# PDB.net
KiCad netlist of a schematic drawn in EAGLE
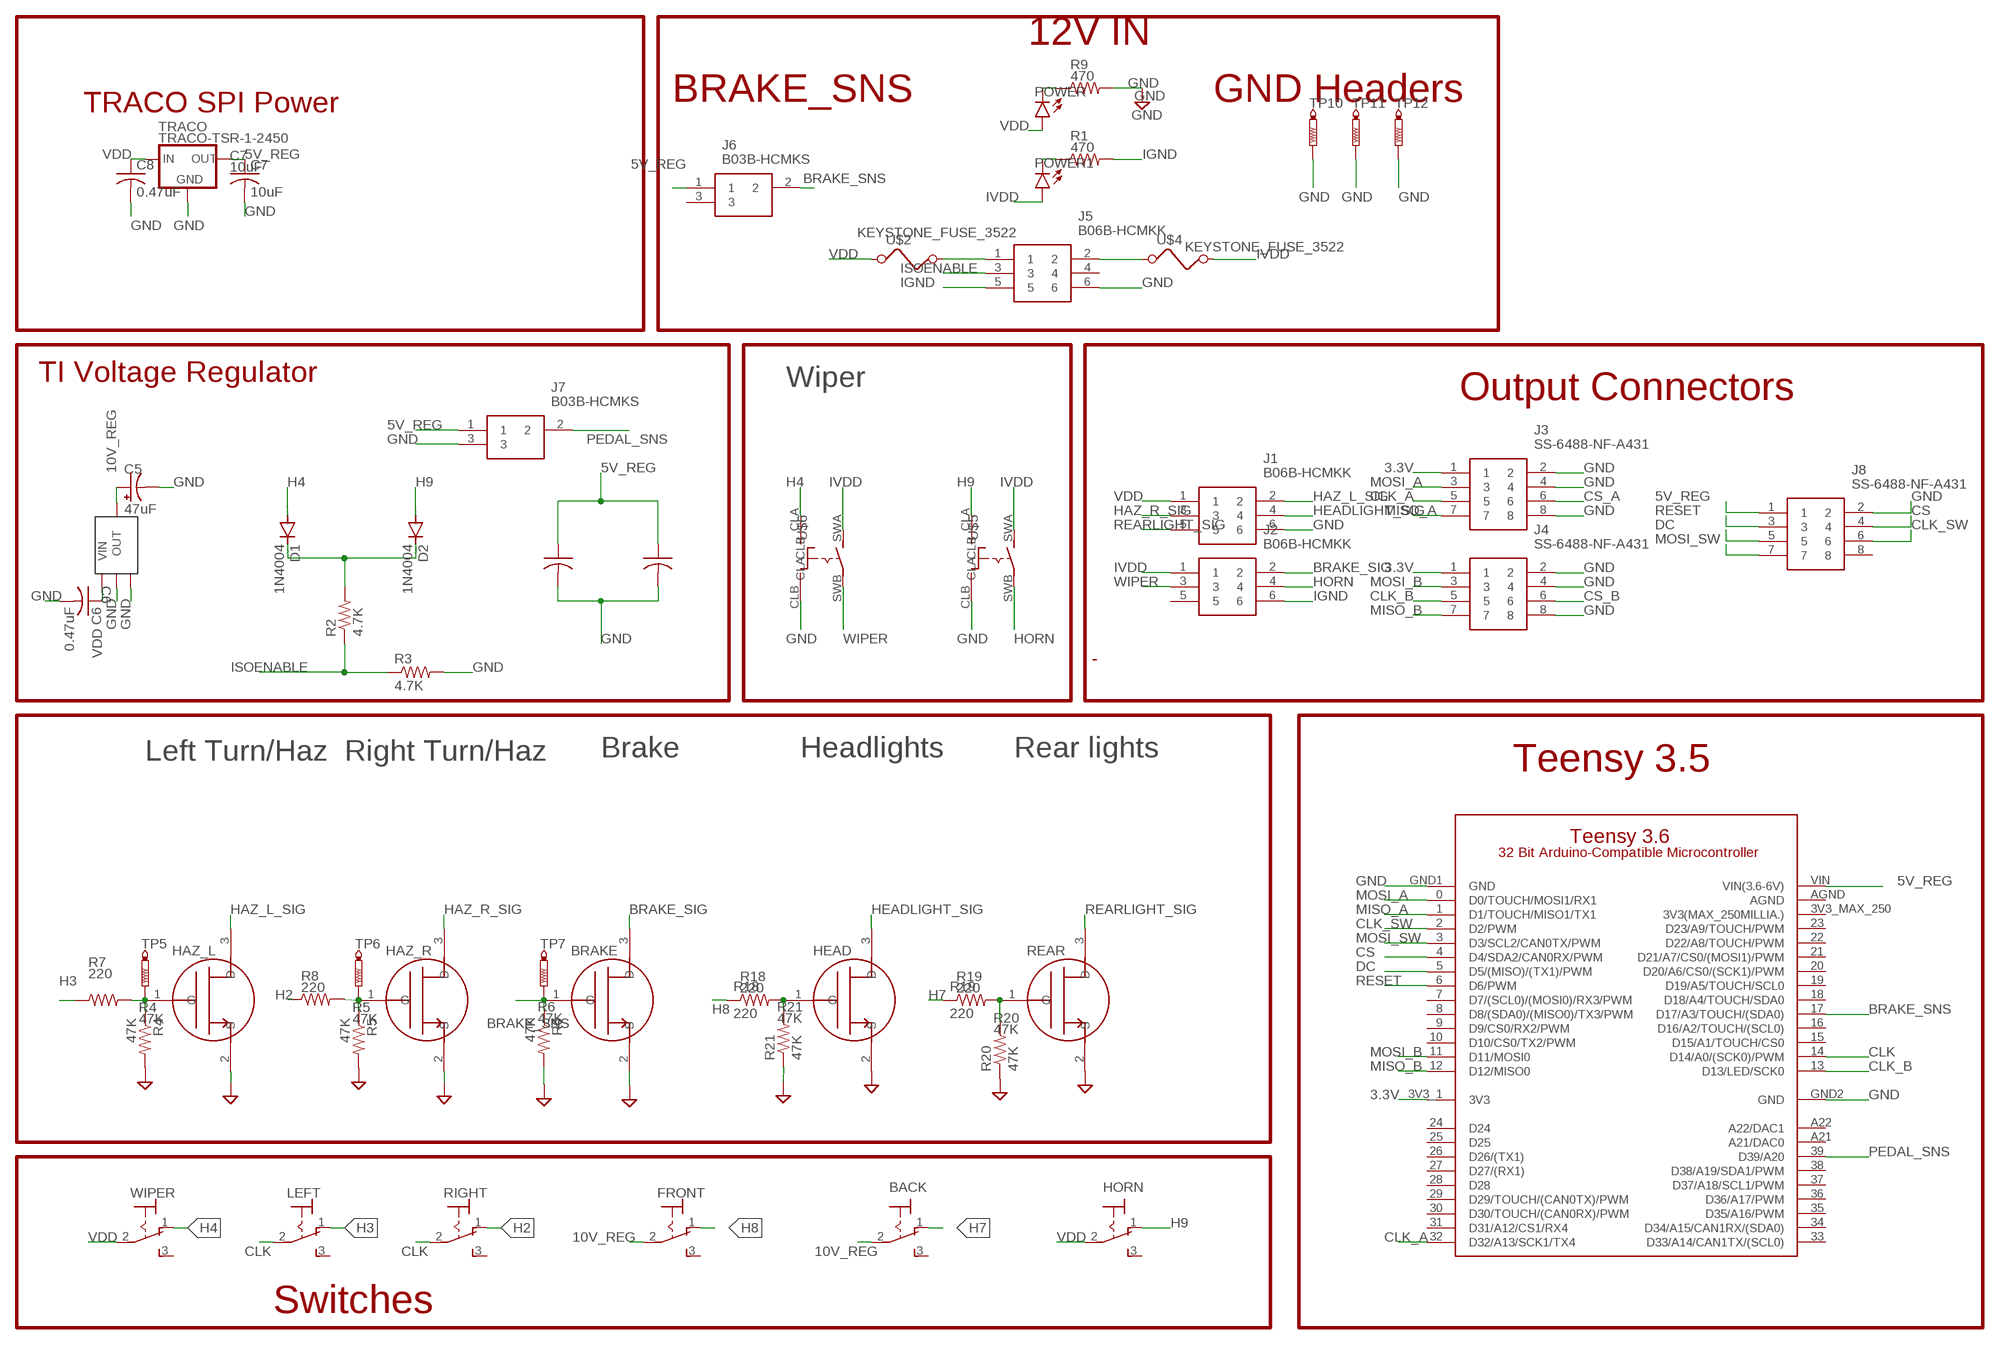
[diagram p0: schematic, sheet 1]

(export (version "E")
  (design (tool "Eeschema 10.0.6"))
  (components
    (comp (ref "BACK")
      (value "M9040P")
      (footprint "eagle-import:M9040P")
      (libsource (lib "eagle-import") (part "M9040P"))
    )
    (comp (ref "BRAKE")
      (value "NCV8405ADPAK-3PIN")
      (footprint "eagle-import:TO254P1054X240-3")
      (libsource (lib "eagle-import") (part "NCV8405ADPAK-3PIN"))
    )
    (comp (ref "C1")
      (value "0.1uF")
      (footprint "eagle-import:C0805")
      (libsource (lib "eagle-import") (part "C-USC0805"))
    )
    (comp (ref "C2")
      (value "10uF")
      (footprint "eagle-import:C0805")
      (libsource (lib "eagle-import") (part "C-USC0805"))
    )
    (comp (ref "C5")
      (value "47uF")
      (footprint "eagle-import:PANASONIC_C")
      (libsource (lib "eagle-import") (part "22UF-POLAR-PANASONIC_C-35V-20%"))
    )
    (comp (ref "C6")
      (value "0.47uF")
      (footprint "eagle-import:C0805")
      (libsource (lib "eagle-import") (part "C-USC0805"))
    )
    (comp (ref "C7")
      (value "10uF")
      (footprint "eagle-import:C0805")
      (libsource (lib "eagle-import") (part "C-USC0805"))
    )
    (comp (ref "C8")
      (value "0.47uF")
      (footprint "eagle-import:C0805")
      (libsource (lib "eagle-import") (part "C-USC0805"))
    )
    (comp (ref "D1")
      (value "1N4004")
      (footprint "eagle-import:DO41-10")
      (libsource (lib "eagle-import") (part "1N4004"))
    )
    (comp (ref "D2")
      (value "1N4004")
      (footprint "eagle-import:DO41-10")
      (libsource (lib "eagle-import") (part "1N4004"))
    )
    (comp (ref "FRONT")
      (value "M9040P")
      (footprint "eagle-import:M9040P")
      (libsource (lib "eagle-import") (part "M9040P"))
    )
    (comp (ref "HAZ_L")
      (value "NCV8405ADPAK-3PIN")
      (footprint "eagle-import:TO254P1054X240-3")
      (libsource (lib "eagle-import") (part "NCV8405ADPAK-3PIN"))
    )
    (comp (ref "HAZ_R")
      (value "NCV8405ADPAK-3PIN")
      (footprint "eagle-import:TO254P1054X240-3")
      (libsource (lib "eagle-import") (part "NCV8405ADPAK-3PIN"))
    )
    (comp (ref "HEAD")
      (value "NCV8405ADPAK-3PIN")
      (footprint "eagle-import:TO254P1054X240-3")
      (libsource (lib "eagle-import") (part "NCV8405ADPAK-3PIN"))
    )
    (comp (ref "HORN")
      (value "M9040P")
      (footprint "eagle-import:M9040P")
      (libsource (lib "eagle-import") (part "M9040P"))
    )
    (comp (ref "J1")
      (value "B06B-HCMKK")
      (footprint "eagle-import:B06BHCMKK")
      (fields (field (name "MOUSER_PART_NUMBER") "306-B06B-HCMKK"))
      (libsource (lib "eagle-import") (part "B06B-HCMKK"))
    )
    (comp (ref "J2")
      (value "B06B-HCMKK")
      (footprint "eagle-import:B06BHCMKK")
      (fields (field (name "MOUSER_PART_NUMBER") "306-B06B-HCMKK"))
      (libsource (lib "eagle-import") (part "B06B-HCMKK"))
    )
    (comp (ref "J3")
      (value "SS-6488-NF-A431")
      (footprint "eagle-import:SS6488NFA431")
      (fields (field (name "MOUSER_PART_NUMBER") "530-SS-6488-NF-A431"))
      (libsource (lib "eagle-import") (part "SS-6488-NF-A431"))
    )
    (comp (ref "J4")
      (value "SS-6488-NF-A431")
      (footprint "eagle-import:SS6488NFA431")
      (fields (field (name "MOUSER_PART_NUMBER") "530-SS-6488-NF-A431"))
      (libsource (lib "eagle-import") (part "SS-6488-NF-A431"))
    )
    (comp (ref "J5")
      (value "B06B-HCMKK")
      (footprint "eagle-import:B06BHCMKK")
      (fields (field (name "MOUSER_PART_NUMBER") "306-B06B-HCMKK"))
      (libsource (lib "eagle-import") (part "B06B-HCMKK"))
    )
    (comp (ref "J6")
      (value "B03B-HCMKS")
      (footprint "eagle-import:B03BHCMKS")
      (fields (field (name "MOUSER_PART_NUMBER") "306-B03B-HCMKS"))
      (libsource (lib "eagle-import") (part "B03B-HCMKS"))
    )
    (comp (ref "J7")
      (value "B03B-HCMKS")
      (footprint "eagle-import:B03BHCMKS")
      (fields (field (name "MOUSER_PART_NUMBER") "306-B03B-HCMKS"))
      (libsource (lib "eagle-import") (part "B03B-HCMKS"))
    )
    (comp (ref "J8")
      (value "SS-6488-NF-A431")
      (footprint "eagle-import:SS6488NFA431")
      (fields (field (name "MOUSER_PART_NUMBER") "530-SS-6488-NF-A431"))
      (libsource (lib "eagle-import") (part "SS-6488-NF-A431"))
    )
    (comp (ref "LEFT")
      (value "M9040P")
      (footprint "eagle-import:M9040P")
      (libsource (lib "eagle-import") (part "M9040P"))
    )
    (comp (ref "LM2940")
      (value "LM2940LM")
      (footprint "eagle-import:SOT230P700X180-4")
      (libsource (lib "eagle-import") (part "LM2940LM"))
    )
    (comp (ref "POWER")
      (value "LEDCHIPLED_0805")
      (footprint "eagle-import:CHIPLED_0805")
      (libsource (lib "eagle-import") (part "LEDCHIPLED_0805"))
    )
    (comp (ref "POWER1")
      (value "LEDCHIPLED_0805")
      (footprint "eagle-import:CHIPLED_0805")
      (libsource (lib "eagle-import") (part "LEDCHIPLED_0805"))
    )
    (comp (ref "R1")
      (value "470")
      (footprint "eagle-import:R3225")
      (libsource (lib "eagle-import") (part "resistor_348_R-US_R3225"))
    )
    (comp (ref "R2")
      (value "4.7K")
      (footprint "eagle-import:R0805")
      (libsource (lib "eagle-import") (part "R-US_R0805"))
    )
    (comp (ref "R3")
      (value "4.7K")
      (footprint "eagle-import:R0805")
      (libsource (lib "eagle-import") (part "R-US_R0805"))
    )
    (comp (ref "R4")
      (value "47K")
      (footprint "eagle-import:R0805")
      (libsource (lib "eagle-import") (part "rcl_334_R-US_R0805"))
    )
    (comp (ref "R5")
      (value "47K")
      (footprint "eagle-import:R0805")
      (libsource (lib "eagle-import") (part "rcl_334_R-US_R0805"))
    )
    (comp (ref "R6")
      (value "47K")
      (footprint "eagle-import:R0805")
      (libsource (lib "eagle-import") (part "rcl_334_R-US_R0805"))
    )
    (comp (ref "R7")
      (value "220")
      (footprint "eagle-import:R0805")
      (libsource (lib "eagle-import") (part "R-US_R0805"))
    )
    (comp (ref "R8")
      (value "220")
      (footprint "eagle-import:R0805")
      (libsource (lib "eagle-import") (part "R-US_R0805"))
    )
    (comp (ref "R9")
      (value "470")
      (footprint "eagle-import:R3225")
      (libsource (lib "eagle-import") (part "resistor_348_R-US_R3225"))
    )
    (comp (ref "R18")
      (value "220")
      (footprint "eagle-import:R0805")
      (libsource (lib "eagle-import") (part "rcl_334_R-US_R0805"))
    )
    (comp (ref "R19")
      (value "220")
      (footprint "eagle-import:R0805")
      (libsource (lib "eagle-import") (part "rcl_334_R-US_R0805"))
    )
    (comp (ref "R20")
      (value "47K")
      (footprint "eagle-import:R0805")
      (libsource (lib "eagle-import") (part "rcl_334_R-US_R0805"))
    )
    (comp (ref "R21")
      (value "47K")
      (footprint "eagle-import:R0805")
      (libsource (lib "eagle-import") (part "rcl_334_R-US_R0805"))
    )
    (comp (ref "REAR")
      (value "NCV8405ADPAK-3PIN")
      (footprint "eagle-import:TO254P1054X240-3")
      (libsource (lib "eagle-import") (part "NCV8405ADPAK-3PIN"))
    )
    (comp (ref "RIGHT")
      (value "M9040P")
      (footprint "eagle-import:M9040P")
      (libsource (lib "eagle-import") (part "M9040P"))
    )
    (comp (ref "TP5")
      (value "PTR1B2,54")
      (footprint "eagle-import:B2,54")
      (libsource (lib "eagle-import") (part "PTR1B2,54"))
    )
    (comp (ref "TP6")
      (value "PTR1B2,54")
      (footprint "eagle-import:B2,54")
      (libsource (lib "eagle-import") (part "PTR1B2,54"))
    )
    (comp (ref "TP7")
      (value "PTR1B2,54")
      (footprint "eagle-import:B2,54")
      (libsource (lib "eagle-import") (part "PTR1B2,54"))
    )
    (comp (ref "TP10")
      (value "PTR1PAD1-13Y")
      (footprint "eagle-import:P1-13Y")
      (libsource (lib "eagle-import") (part "PTR1PAD1-13Y"))
    )
    (comp (ref "TP11")
      (value "PTR1PAD1-13Y")
      (footprint "eagle-import:P1-13Y")
      (libsource (lib "eagle-import") (part "PTR1PAD1-13Y"))
    )
    (comp (ref "TP12")
      (value "PTR1PAD1-13Y")
      (footprint "eagle-import:P1-13Y")
      (libsource (lib "eagle-import") (part "PTR1PAD1-13Y"))
    )
    (comp (ref "TRACO")
      (value "TRACO-TSR-1-2450")
      (footprint "eagle-import:SIP3")
      (libsource (lib "eagle-import") (part "TRACO-TSR-1-2450"))
    )
    (comp (ref "U$2")
      (value "KEYSTONE_FUSE_3522")
      (footprint "eagle-import:KEYSTONE_FUSE_3522")
      (libsource (lib "eagle-import") (part "KEYSTONE_FUSE_3522"))
    )
    (comp (ref "U$3")
      (value "TEENSY-3.6_ONLY_HOLES")
      (footprint "eagle-import:TEENSY-3.6_ONLY_HOLES")
      (libsource (lib "eagle-import") (part "TEENSY-3.6_ONLY_HOLES"))
    )
    (comp (ref "U$4")
      (value "KEYSTONE_FUSE_3522")
      (footprint "eagle-import:KEYSTONE_FUSE_3522")
      (libsource (lib "eagle-import") (part "KEYSTONE_FUSE_3522"))
    )
    (comp (ref "U$5")
      (value "TE_CON_OJE-SH-112DM,095\\")
      (footprint "eagle-import:TE_CON_OJE-SH-112DM,095")
      (libsource (lib "eagle-import") (part "TE_CON_OJE-SH-112DM,095{backslash}"))
    )
    (comp (ref "U$6")
      (value "TE_CON_OJE-SH-112DM,095\\")
      (footprint "eagle-import:TE_CON_OJE-SH-112DM,095")
      (libsource (lib "eagle-import") (part "TE_CON_OJE-SH-112DM,095{backslash}"))
    )
    (comp (ref "WIPER")
      (value "M9040P")
      (footprint "eagle-import:M9040P")
      (libsource (lib "eagle-import") (part "M9040P"))
    )
  )
  (nets
    (net (code "1") (name "3.3V") (class "Default")
      (node (ref "J3") (pin "1") (pinfunction "1_1") (pintype "bidirectional"))
      (node (ref "J4") (pin "1") (pinfunction "1_1") (pintype "bidirectional"))
      (node (ref "U$3") (pin "3V3_1") (pinfunction "3V3_3V3_1") (pintype "power_in"))
    )
    (net (code "2") (name "5V_REG") (class "Default")
      (node (ref "C1") (pin "1") (pinfunction "1_1") (pintype "passive"))
      (node (ref "C2") (pin "1") (pinfunction "1_1") (pintype "passive"))
      (node (ref "C7") (pin "1") (pinfunction "1_1") (pintype "passive"))
      (node (ref "J6") (pin "1") (pinfunction "1_1") (pintype "bidirectional"))
      (node (ref "J7") (pin "1") (pinfunction "1_1") (pintype "bidirectional"))
      (node (ref "J8") (pin "1") (pinfunction "1_1") (pintype "bidirectional"))
      (node (ref "TRACO") (pin "3") (pinfunction "OUT_3") (pintype "passive"))
      (node (ref "U$3") (pin "VIN") (pinfunction "VIN(3.6-6V)_VIN") (pintype "power_in"))
    )
    (net (code "3") (name "10V_REG") (class "Default")
      (node (ref "BACK") (pin "2") (pinfunction "P_2") (pintype "passive"))
      (node (ref "C5") (pin "+") (pinfunction "+_+") (pintype "passive"))
      (node (ref "FRONT") (pin "2") (pinfunction "P_2") (pintype "passive"))
      (node (ref "LM2940") (pin "3") (pinfunction "OUT_3") (pintype "output"))
    )
    (net (code "4") (name "AGND") (class "Default")
      (node (ref "U$3") (pin "AGND") (pinfunction "AGND_AGND") (pintype "power_in"))
    )
    (net (code "5") (name "BRAKE_SIG") (class "Default")
      (node (ref "BRAKE") (pin "3") (pinfunction "D_3") (pintype "bidirectional"))
      (node (ref "J2") (pin "2") (pinfunction "2_2") (pintype "bidirectional"))
    )
    (net (code "6") (name "BRAKE_SNS") (class "Default")
      (node (ref "BRAKE") (pin "1") (pinfunction "G_1") (pintype "bidirectional"))
      (node (ref "J6") (pin "2") (pinfunction "2_2") (pintype "bidirectional"))
      (node (ref "R6") (pin "1") (pinfunction "1_1") (pintype "passive"))
      (node (ref "TP7") (pin "TP") (pinfunction "TP_TP") (pintype "input"))
      (node (ref "U$3") (pin "17") (pinfunction "D17/A3/TOUCH/(SDA0)_17") (pintype "bidirectional"))
    )
    (net (code "7") (name "CLK") (class "Default")
      (node (ref "LEFT") (pin "2") (pinfunction "P_2") (pintype "passive"))
      (node (ref "RIGHT") (pin "2") (pinfunction "P_2") (pintype "passive"))
      (node (ref "U$3") (pin "14") (pinfunction "D14/A0/(SCK0)/PWM_14") (pintype "bidirectional"))
    )
    (net (code "8") (name "CLK_A") (class "Default")
      (node (ref "J3") (pin "5") (pinfunction "5_5") (pintype "bidirectional"))
      (node (ref "U$3") (pin "32") (pinfunction "D32/A13/SCK1/TX4_32") (pintype "bidirectional"))
    )
    (net (code "9") (name "CLK_B") (class "Default")
      (node (ref "J4") (pin "5") (pinfunction "5_5") (pintype "bidirectional"))
      (node (ref "U$3") (pin "13") (pinfunction "D13/LED/SCK0_13") (pintype "bidirectional"))
    )
    (net (code "10") (name "CLK_SW") (class "Default")
      (node (ref "J8") (pin "6") (pinfunction "6_6") (pintype "bidirectional"))
      (node (ref "U$3") (pin "2") (pinfunction "D2/PWM_2") (pintype "bidirectional"))
    )
    (net (code "11") (name "CS") (class "Default")
      (node (ref "J8") (pin "4") (pinfunction "4_4") (pintype "bidirectional"))
      (node (ref "U$3") (pin "4") (pinfunction "D4/SDA2/CAN0RX/PWM_4") (pintype "bidirectional"))
    )
    (net (code "12") (name "CS_A") (class "Default")
      (node (ref "J3") (pin "6") (pinfunction "6_6") (pintype "bidirectional"))
    )
    (net (code "13") (name "CS_B") (class "Default")
      (node (ref "J4") (pin "6") (pinfunction "6_6") (pintype "bidirectional"))
    )
    (net (code "14") (name "DC") (class "Default")
      (node (ref "J8") (pin "5") (pinfunction "5_5") (pintype "bidirectional"))
      (node (ref "U$3") (pin "5") (pinfunction "D5/(MISO)/(TX1)/PWM_5") (pintype "bidirectional"))
    )
    (net (code "15") (name "GND") (class "Default")
      (node (ref "BRAKE") (pin "2") (pinfunction "S_2") (pintype "bidirectional"))
      (node (ref "C1") (pin "2") (pinfunction "2_2") (pintype "passive"))
      (node (ref "C2") (pin "2") (pinfunction "2_2") (pintype "passive"))
      (node (ref "C5") (pin "-") (pinfunction "-_-") (pintype "passive"))
      (node (ref "C6") (pin "2") (pinfunction "2_2") (pintype "passive"))
      (node (ref "C7") (pin "2") (pinfunction "2_2") (pintype "passive"))
      (node (ref "C8") (pin "2") (pinfunction "2_2") (pintype "passive"))
      (node (ref "HAZ_L") (pin "2") (pinfunction "S_2") (pintype "bidirectional"))
      (node (ref "HAZ_R") (pin "2") (pinfunction "S_2") (pintype "bidirectional"))
      (node (ref "HEAD") (pin "2") (pinfunction "S_2") (pintype "bidirectional"))
      (node (ref "J1") (pin "6") (pinfunction "6_6") (pintype "bidirectional"))
      (node (ref "J3") (pin "2") (pinfunction "2_2") (pintype "bidirectional"))
      (node (ref "J3") (pin "4") (pinfunction "4_4") (pintype "bidirectional"))
      (node (ref "J3") (pin "8") (pinfunction "8_8") (pintype "bidirectional"))
      (node (ref "J4") (pin "2") (pinfunction "2_2") (pintype "bidirectional"))
      (node (ref "J4") (pin "4") (pinfunction "4_4") (pintype "bidirectional"))
      (node (ref "J4") (pin "8") (pinfunction "8_8") (pintype "bidirectional"))
      (node (ref "J5") (pin "6") (pinfunction "6_6") (pintype "bidirectional"))
      (node (ref "J7") (pin "3") (pinfunction "3_3") (pintype "bidirectional"))
      (node (ref "J8") (pin "2") (pinfunction "2_2") (pintype "bidirectional"))
      (node (ref "LM2940") (pin "2") (pinfunction "GND2_2") (pintype "power_in"))
      (node (ref "LM2940") (pin "4") (pinfunction "GND_4") (pintype "power_in"))
      (node (ref "R20") (pin "1") (pinfunction "1_1") (pintype "passive"))
      (node (ref "R21") (pin "1") (pinfunction "1_1") (pintype "passive"))
      (node (ref "R3") (pin "2") (pinfunction "2_2") (pintype "passive"))
      (node (ref "R4") (pin "2") (pinfunction "2_2") (pintype "passive"))
      (node (ref "R5") (pin "2") (pinfunction "2_2") (pintype "passive"))
      (node (ref "R6") (pin "2") (pinfunction "2_2") (pintype "passive"))
      (node (ref "R9") (pin "2") (pinfunction "2_2") (pintype "passive"))
      (node (ref "REAR") (pin "2") (pinfunction "S_2") (pintype "bidirectional"))
      (node (ref "TP10") (pin "TP") (pinfunction "TP_TP") (pintype "input"))
      (node (ref "TP11") (pin "TP") (pinfunction "TP_TP") (pintype "input"))
      (node (ref "TP12") (pin "TP") (pinfunction "TP_TP") (pintype "input"))
      (node (ref "TRACO") (pin "2") (pinfunction "GND_2") (pintype "input"))
      (node (ref "U$3") (pin "GND1") (pinfunction "GND_GND1") (pintype "power_in"))
      (node (ref "U$3") (pin "GND2") (pinfunction "GND_GND2") (pintype "power_in"))
      (node (ref "U$5") (pin "CLB") (pinfunction "CLB_CLB") (pintype "bidirectional"))
      (node (ref "U$6") (pin "CLB") (pinfunction "CLB_CLB") (pintype "bidirectional"))
    )
    (net (code "16") (name "H2") (class "Default")
      (node (ref "R8") (pin "1") (pinfunction "1_1") (pintype "passive"))
      (node (ref "RIGHT") (pin "1") (pinfunction "O_1") (pintype "passive"))
    )
    (net (code "17") (name "H3") (class "Default")
      (node (ref "LEFT") (pin "1") (pinfunction "O_1") (pintype "passive"))
      (node (ref "R7") (pin "1") (pinfunction "1_1") (pintype "passive"))
    )
    (net (code "18") (name "H4") (class "Default")
      (node (ref "D1") (pin "A") (pinfunction "A_A") (pintype "passive"))
      (node (ref "U$6") (pin "CLA") (pinfunction "CLA_CLA") (pintype "bidirectional"))
      (node (ref "WIPER") (pin "1") (pinfunction "O_1") (pintype "passive"))
    )
    (net (code "19") (name "H7") (class "Default")
      (node (ref "BACK") (pin "1") (pinfunction "O_1") (pintype "passive"))
      (node (ref "R19") (pin "1") (pinfunction "1_1") (pintype "passive"))
    )
    (net (code "20") (name "H8") (class "Default")
      (node (ref "FRONT") (pin "1") (pinfunction "O_1") (pintype "passive"))
      (node (ref "R18") (pin "1") (pinfunction "1_1") (pintype "passive"))
    )
    (net (code "21") (name "H9") (class "Default")
      (node (ref "D2") (pin "A") (pinfunction "A_A") (pintype "passive"))
      (node (ref "HORN") (pin "1") (pinfunction "O_1") (pintype "passive"))
      (node (ref "U$5") (pin "CLA") (pinfunction "CLA_CLA") (pintype "bidirectional"))
    )
    (net (code "22") (name "HAZ_L_SIG") (class "Default")
      (node (ref "HAZ_L") (pin "3") (pinfunction "D_3") (pintype "bidirectional"))
      (node (ref "J1") (pin "2") (pinfunction "2_2") (pintype "bidirectional"))
    )
    (net (code "23") (name "HAZ_R_SIG") (class "Default")
      (node (ref "HAZ_R") (pin "3") (pinfunction "D_3") (pintype "bidirectional"))
      (node (ref "J1") (pin "3") (pinfunction "3_3") (pintype "bidirectional"))
    )
    (net (code "24") (name "HEADLIGHT_SIG") (class "Default")
      (node (ref "HEAD") (pin "3") (pinfunction "D_3") (pintype "bidirectional"))
      (node (ref "J1") (pin "4") (pinfunction "4_4") (pintype "bidirectional"))
    )
    (net (code "25") (name "HORN") (class "Default")
      (node (ref "J2") (pin "4") (pinfunction "4_4") (pintype "bidirectional"))
      (node (ref "U$5") (pin "SWB") (pinfunction "SWB_SWB") (pintype "passive"))
    )
    (net (code "26") (name "IGND") (class "Default")
      (node (ref "J2") (pin "6") (pinfunction "6_6") (pintype "bidirectional"))
      (node (ref "J5") (pin "5") (pinfunction "5_5") (pintype "bidirectional"))
      (node (ref "R1") (pin "2") (pinfunction "2_2") (pintype "passive"))
    )
    (net (code "27") (name "ISOENABLE") (class "Default")
      (node (ref "J5") (pin "3") (pinfunction "3_3") (pintype "bidirectional"))
      (node (ref "R2") (pin "1") (pinfunction "1_1") (pintype "passive"))
      (node (ref "R3") (pin "1") (pinfunction "1_1") (pintype "passive"))
    )
    (net (code "28") (name "IVDD") (class "Default")
      (node (ref "J2") (pin "1") (pinfunction "1_1") (pintype "bidirectional"))
      (node (ref "POWER1") (pin "A") (pinfunction "A_A") (pintype "passive"))
      (node (ref "U$4") (pin "B1") (pinfunction "2_B1") (pintype "passive"))
      (node (ref "U$4") (pin "B2") (pinfunction "2_B2") (pintype "passive"))
      (node (ref "U$5") (pin "SWA") (pinfunction "SWA_SWA") (pintype "passive"))
      (node (ref "U$6") (pin "SWA") (pinfunction "SWA_SWA") (pintype "passive"))
    )
    (net (code "29") (name "MISO_A") (class "Default")
      (node (ref "J3") (pin "7") (pinfunction "7_7") (pintype "bidirectional"))
      (node (ref "U$3") (pin "1") (pinfunction "D1/TOUCH/MISO1/TX1_1") (pintype "bidirectional"))
    )
    (net (code "30") (name "MISO_B") (class "Default")
      (node (ref "J4") (pin "7") (pinfunction "7_7") (pintype "bidirectional"))
      (node (ref "U$3") (pin "12") (pinfunction "D12/MISO0_12") (pintype "bidirectional"))
    )
    (net (code "31") (name "MOSI_A") (class "Default")
      (node (ref "J3") (pin "3") (pinfunction "3_3") (pintype "bidirectional"))
      (node (ref "U$3") (pin "0") (pinfunction "D0/TOUCH/MOSI1/RX1_0") (pintype "bidirectional"))
    )
    (net (code "32") (name "MOSI_B") (class "Default")
      (node (ref "J4") (pin "3") (pinfunction "3_3") (pintype "bidirectional"))
      (node (ref "U$3") (pin "11") (pinfunction "D11/MOSI0_11") (pintype "bidirectional"))
    )
    (net (code "33") (name "MOSI_SW") (class "Default")
      (node (ref "J8") (pin "7") (pinfunction "7_7") (pintype "bidirectional"))
      (node (ref "U$3") (pin "3") (pinfunction "D3/SCL2/CAN0TX/PWM_3") (pintype "bidirectional"))
    )
    (net (code "34") (name "Net-(D1-PadC)") (class "Default")
      (node (ref "D1") (pin "C") (pinfunction "C_C") (pintype "passive"))
      (node (ref "D2") (pin "C") (pinfunction "C_C") (pintype "passive"))
      (node (ref "R2") (pin "2") (pinfunction "2_2") (pintype "passive"))
    )
    (net (code "35") (name "Net-(HAZ_L-G)") (class "Default")
      (node (ref "HAZ_L") (pin "1") (pinfunction "G_1") (pintype "bidirectional"))
      (node (ref "R4") (pin "1") (pinfunction "1_1") (pintype "passive"))
      (node (ref "R7") (pin "2") (pinfunction "2_2") (pintype "passive"))
      (node (ref "TP5") (pin "TP") (pinfunction "TP_TP") (pintype "input"))
    )
    (net (code "36") (name "Net-(HAZ_R-G)") (class "Default")
      (node (ref "HAZ_R") (pin "1") (pinfunction "G_1") (pintype "bidirectional"))
      (node (ref "R5") (pin "1") (pinfunction "1_1") (pintype "passive"))
      (node (ref "R8") (pin "2") (pinfunction "2_2") (pintype "passive"))
      (node (ref "TP6") (pin "TP") (pinfunction "TP_TP") (pintype "input"))
    )
    (net (code "37") (name "Net-(HEAD-G)") (class "Default")
      (node (ref "HEAD") (pin "1") (pinfunction "G_1") (pintype "bidirectional"))
      (node (ref "R18") (pin "2") (pinfunction "2_2") (pintype "passive"))
      (node (ref "R21") (pin "2") (pinfunction "2_2") (pintype "passive"))
    )
    (net (code "38") (name "Net-(J5-Pad1)") (class "Default")
      (node (ref "J5") (pin "1") (pinfunction "1_1") (pintype "bidirectional"))
      (node (ref "U$2") (pin "B1") (pinfunction "2_B1") (pintype "passive"))
      (node (ref "U$2") (pin "B2") (pinfunction "2_B2") (pintype "passive"))
    )
    (net (code "39") (name "Net-(J5-Pad2)") (class "Default")
      (node (ref "J5") (pin "2") (pinfunction "2_2") (pintype "bidirectional"))
      (node (ref "U$4") (pin "A1") (pinfunction "1_A1") (pintype "passive"))
      (node (ref "U$4") (pin "A2") (pinfunction "1_A2") (pintype "passive"))
    )
    (net (code "40") (name "Net-(POWER-PadC)") (class "Default")
      (node (ref "POWER") (pin "C") (pinfunction "C_C") (pintype "passive"))
      (node (ref "R9") (pin "1") (pinfunction "1_1") (pintype "passive"))
    )
    (net (code "41") (name "Net-(POWER1-PadC)") (class "Default")
      (node (ref "POWER1") (pin "C") (pinfunction "C_C") (pintype "passive"))
      (node (ref "R1") (pin "1") (pinfunction "1_1") (pintype "passive"))
    )
    (net (code "42") (name "Net-(REAR-G)") (class "Default")
      (node (ref "R19") (pin "2") (pinfunction "2_2") (pintype "passive"))
      (node (ref "R20") (pin "2") (pinfunction "2_2") (pintype "passive"))
      (node (ref "REAR") (pin "1") (pinfunction "G_1") (pintype "bidirectional"))
    )
    (net (code "43") (name "PEDAL_SNS") (class "Default")
      (node (ref "J7") (pin "2") (pinfunction "2_2") (pintype "bidirectional"))
      (node (ref "U$3") (pin "39") (pinfunction "D39/A20_39") (pintype "bidirectional"))
    )
    (net (code "44") (name "REARLIGHT_SIG") (class "Default")
      (node (ref "J1") (pin "5") (pinfunction "5_5") (pintype "bidirectional"))
      (node (ref "REAR") (pin "3") (pinfunction "D_3") (pintype "bidirectional"))
    )
    (net (code "45") (name "RESET") (class "Default")
      (node (ref "J8") (pin "3") (pinfunction "3_3") (pintype "bidirectional"))
      (node (ref "U$3") (pin "6") (pinfunction "D6/PWM_6") (pintype "bidirectional"))
    )
    (net (code "46") (name "VDD") (class "Default")
      (node (ref "C6") (pin "1") (pinfunction "1_1") (pintype "passive"))
      (node (ref "C8") (pin "1") (pinfunction "1_1") (pintype "passive"))
      (node (ref "HORN") (pin "2") (pinfunction "P_2") (pintype "passive"))
      (node (ref "J1") (pin "1") (pinfunction "1_1") (pintype "bidirectional"))
      (node (ref "LM2940") (pin "1") (pinfunction "VIN_1") (pintype "input"))
      (node (ref "POWER") (pin "A") (pinfunction "A_A") (pintype "passive"))
      (node (ref "TRACO") (pin "1") (pinfunction "IN_1") (pintype "input"))
      (node (ref "U$2") (pin "A1") (pinfunction "1_A1") (pintype "passive"))
      (node (ref "U$2") (pin "A2") (pinfunction "1_A2") (pintype "passive"))
      (node (ref "WIPER") (pin "2") (pinfunction "P_2") (pintype "passive"))
    )
    (net (code "47") (name "WIPER") (class "Default")
      (node (ref "J2") (pin "3") (pinfunction "3_3") (pintype "bidirectional"))
      (node (ref "U$6") (pin "SWB") (pinfunction "SWB_SWB") (pintype "passive"))
    )
    (net (code "48") (name "unconnected-(BACK-S-Pad3)") (class "Default")
      (node (ref "BACK") (pin "3") (pinfunction "S_3") (pintype "passive"))
    )
    (net (code "49") (name "unconnected-(FRONT-S-Pad3)") (class "Default")
      (node (ref "FRONT") (pin "3") (pinfunction "S_3") (pintype "passive"))
    )
    (net (code "50") (name "unconnected-(HORN-S-Pad3)") (class "Default")
      (node (ref "HORN") (pin "3") (pinfunction "S_3") (pintype "passive"))
    )
    (net (code "51") (name "unconnected-(J2-Pad5)") (class "Default")
      (node (ref "J2") (pin "5") (pinfunction "5_5") (pintype "bidirectional"))
    )
    (net (code "52") (name "unconnected-(J5-Pad4)") (class "Default")
      (node (ref "J5") (pin "4") (pinfunction "4_4") (pintype "bidirectional"))
    )
    (net (code "53") (name "unconnected-(J6-Pad3)") (class "Default")
      (node (ref "J6") (pin "3") (pinfunction "3_3") (pintype "bidirectional"))
    )
    (net (code "54") (name "unconnected-(J8-Pad8)") (class "Default")
      (node (ref "J8") (pin "8") (pinfunction "8_8") (pintype "bidirectional"))
    )
    (net (code "55") (name "unconnected-(LEFT-S-Pad3)") (class "Default")
      (node (ref "LEFT") (pin "3") (pinfunction "S_3") (pintype "passive"))
    )
    (net (code "56") (name "unconnected-(RIGHT-S-Pad3)") (class "Default")
      (node (ref "RIGHT") (pin "3") (pinfunction "S_3") (pintype "passive"))
    )
    (net (code "57") (name "unconnected-(U$3-3V3(MAX_250MILLIA.)-Pad3V3_MAX_250)") (class "Default")
      (node (ref "U$3") (pin "3V3_MAX_250") (pinfunction "3V3(MAX_250MILLIA.)_3V3_MAX_250") (pintype "bidirectional"))
    )
    (net (code "58") (name "unconnected-(U$3-A21{slash}DAC0-PadA21)") (class "Default")
      (node (ref "U$3") (pin "A21") (pinfunction "A21/DAC0_A21") (pintype "bidirectional"))
    )
    (net (code "59") (name "unconnected-(U$3-A22{slash}DAC1-PadA22)") (class "Default")
      (node (ref "U$3") (pin "A22") (pinfunction "A22/DAC1_A22") (pintype "bidirectional"))
    )
    (net (code "60") (name "unconnected-(U$3-D7{slash}(SCL0){slash}(MOSI0){slash}RX3{slash}PWM-Pad7)") (class "Default")
      (node (ref "U$3") (pin "7") (pinfunction "D7/(SCL0)/(MOSI0)/RX3/PWM_7") (pintype "bidirectional"))
    )
    (net (code "61") (name "unconnected-(U$3-D8{slash}(SDA0){slash}(MISO0){slash}TX3{slash}PWM-Pad8)") (class "Default")
      (node (ref "U$3") (pin "8") (pinfunction "D8/(SDA0)/(MISO0)/TX3/PWM_8") (pintype "bidirectional"))
    )
    (net (code "62") (name "unconnected-(U$3-D9{slash}CS0{slash}RX2{slash}PWM-Pad9)") (class "Default")
      (node (ref "U$3") (pin "9") (pinfunction "D9/CS0/RX2/PWM_9") (pintype "bidirectional"))
    )
    (net (code "63") (name "unconnected-(U$3-D10{slash}CS0{slash}TX2{slash}PWM-Pad10)") (class "Default")
      (node (ref "U$3") (pin "10") (pinfunction "D10/CS0/TX2/PWM_10") (pintype "bidirectional"))
    )
    (net (code "64") (name "unconnected-(U$3-D15{slash}A1{slash}TOUCH{slash}CS0-Pad15)") (class "Default")
      (node (ref "U$3") (pin "15") (pinfunction "D15/A1/TOUCH/CS0_15") (pintype "bidirectional"))
    )
    (net (code "65") (name "unconnected-(U$3-D16{slash}A2{slash}TOUCH{slash}(SCL0)-Pad16)") (class "Default")
      (node (ref "U$3") (pin "16") (pinfunction "D16/A2/TOUCH/(SCL0)_16") (pintype "bidirectional"))
    )
    (net (code "66") (name "unconnected-(U$3-D18{slash}A4{slash}TOUCH{slash}SDA0-Pad18)") (class "Default")
      (node (ref "U$3") (pin "18") (pinfunction "D18/A4/TOUCH/SDA0_18") (pintype "bidirectional"))
    )
    (net (code "67") (name "unconnected-(U$3-D19{slash}A5{slash}TOUCH{slash}SCL0-Pad19)") (class "Default")
      (node (ref "U$3") (pin "19") (pinfunction "D19/A5/TOUCH/SCL0_19") (pintype "bidirectional"))
    )
    (net (code "68") (name "unconnected-(U$3-D20{slash}A6{slash}CS0{slash}(SCK1){slash}PWM-Pad20)") (class "Default")
      (node (ref "U$3") (pin "20") (pinfunction "D20/A6/CS0/(SCK1)/PWM_20") (pintype "bidirectional"))
    )
    (net (code "69") (name "unconnected-(U$3-D21{slash}A7{slash}CS0{slash}(MOSI1){slash}PWM-Pad21)") (class "Default")
      (node (ref "U$3") (pin "21") (pinfunction "D21/A7/CS0/(MOSI1)/PWM_21") (pintype "bidirectional"))
    )
    (net (code "70") (name "unconnected-(U$3-D22{slash}A8{slash}TOUCH{slash}PWM-Pad22)") (class "Default")
      (node (ref "U$3") (pin "22") (pinfunction "D22/A8/TOUCH/PWM_22") (pintype "bidirectional"))
    )
    (net (code "71") (name "unconnected-(U$3-D23{slash}A9{slash}TOUCH{slash}PWM-Pad23)") (class "Default")
      (node (ref "U$3") (pin "23") (pinfunction "D23/A9/TOUCH/PWM_23") (pintype "bidirectional"))
    )
    (net (code "72") (name "unconnected-(U$3-D24-Pad24)") (class "Default")
      (node (ref "U$3") (pin "24") (pinfunction "D24_24") (pintype "bidirectional"))
    )
    (net (code "73") (name "unconnected-(U$3-D25-Pad25)") (class "Default")
      (node (ref "U$3") (pin "25") (pinfunction "D25_25") (pintype "bidirectional"))
    )
    (net (code "74") (name "unconnected-(U$3-D26{slash}(TX1)-Pad26)") (class "Default")
      (node (ref "U$3") (pin "26") (pinfunction "D26/(TX1)_26") (pintype "bidirectional"))
    )
    (net (code "75") (name "unconnected-(U$3-D27{slash}(RX1)-Pad27)") (class "Default")
      (node (ref "U$3") (pin "27") (pinfunction "D27/(RX1)_27") (pintype "bidirectional"))
    )
    (net (code "76") (name "unconnected-(U$3-D28-Pad28)") (class "Default")
      (node (ref "U$3") (pin "28") (pinfunction "D28_28") (pintype "bidirectional"))
    )
    (net (code "77") (name "unconnected-(U$3-D29{slash}TOUCH{slash}(CAN0TX){slash}PWM-Pad29)") (class "Default")
      (node (ref "U$3") (pin "29") (pinfunction "D29/TOUCH/(CAN0TX)/PWM_29") (pintype "bidirectional"))
    )
    (net (code "78") (name "unconnected-(U$3-D30{slash}TOUCH{slash}(CAN0RX){slash}PWM-Pad30)") (class "Default")
      (node (ref "U$3") (pin "30") (pinfunction "D30/TOUCH/(CAN0RX)/PWM_30") (pintype "bidirectional"))
    )
    (net (code "79") (name "unconnected-(U$3-D31{slash}A12{slash}CS1{slash}RX4-Pad31)") (class "Default")
      (node (ref "U$3") (pin "31") (pinfunction "D31/A12/CS1/RX4_31") (pintype "bidirectional"))
    )
    (net (code "80") (name "unconnected-(U$3-D33{slash}A14{slash}CAN1TX{slash}(SCL0)-Pad33)") (class "Default")
      (node (ref "U$3") (pin "33") (pinfunction "D33/A14/CAN1TX/(SCL0)_33") (pintype "bidirectional"))
    )
    (net (code "81") (name "unconnected-(U$3-D34{slash}A15{slash}CAN1RX{slash}(SDA0)-Pad34)") (class "Default")
      (node (ref "U$3") (pin "34") (pinfunction "D34/A15/CAN1RX/(SDA0)_34") (pintype "bidirectional"))
    )
    (net (code "82") (name "unconnected-(U$3-D35{slash}A16{slash}PWM-Pad35)") (class "Default")
      (node (ref "U$3") (pin "35") (pinfunction "D35/A16/PWM_35") (pintype "bidirectional"))
    )
    (net (code "83") (name "unconnected-(U$3-D36{slash}A17{slash}PWM-Pad36)") (class "Default")
      (node (ref "U$3") (pin "36") (pinfunction "D36/A17/PWM_36") (pintype "bidirectional"))
    )
    (net (code "84") (name "unconnected-(U$3-D37{slash}A18{slash}SCL1{slash}PWM-Pad37)") (class "Default")
      (node (ref "U$3") (pin "37") (pinfunction "D37/A18/SCL1/PWM_37") (pintype "bidirectional"))
    )
    (net (code "85") (name "unconnected-(U$3-D38{slash}A19{slash}SDA1{slash}PWM-Pad38)") (class "Default")
      (node (ref "U$3") (pin "38") (pinfunction "D38/A19/SDA1/PWM_38") (pintype "bidirectional"))
    )
    (net (code "86") (name "unconnected-(WIPER-S-Pad3)") (class "Default")
      (node (ref "WIPER") (pin "3") (pinfunction "S_3") (pintype "passive"))
    )
  )
)
